# weathervane_public.net
KiCad netlist of a schematic drawn in EAGLE
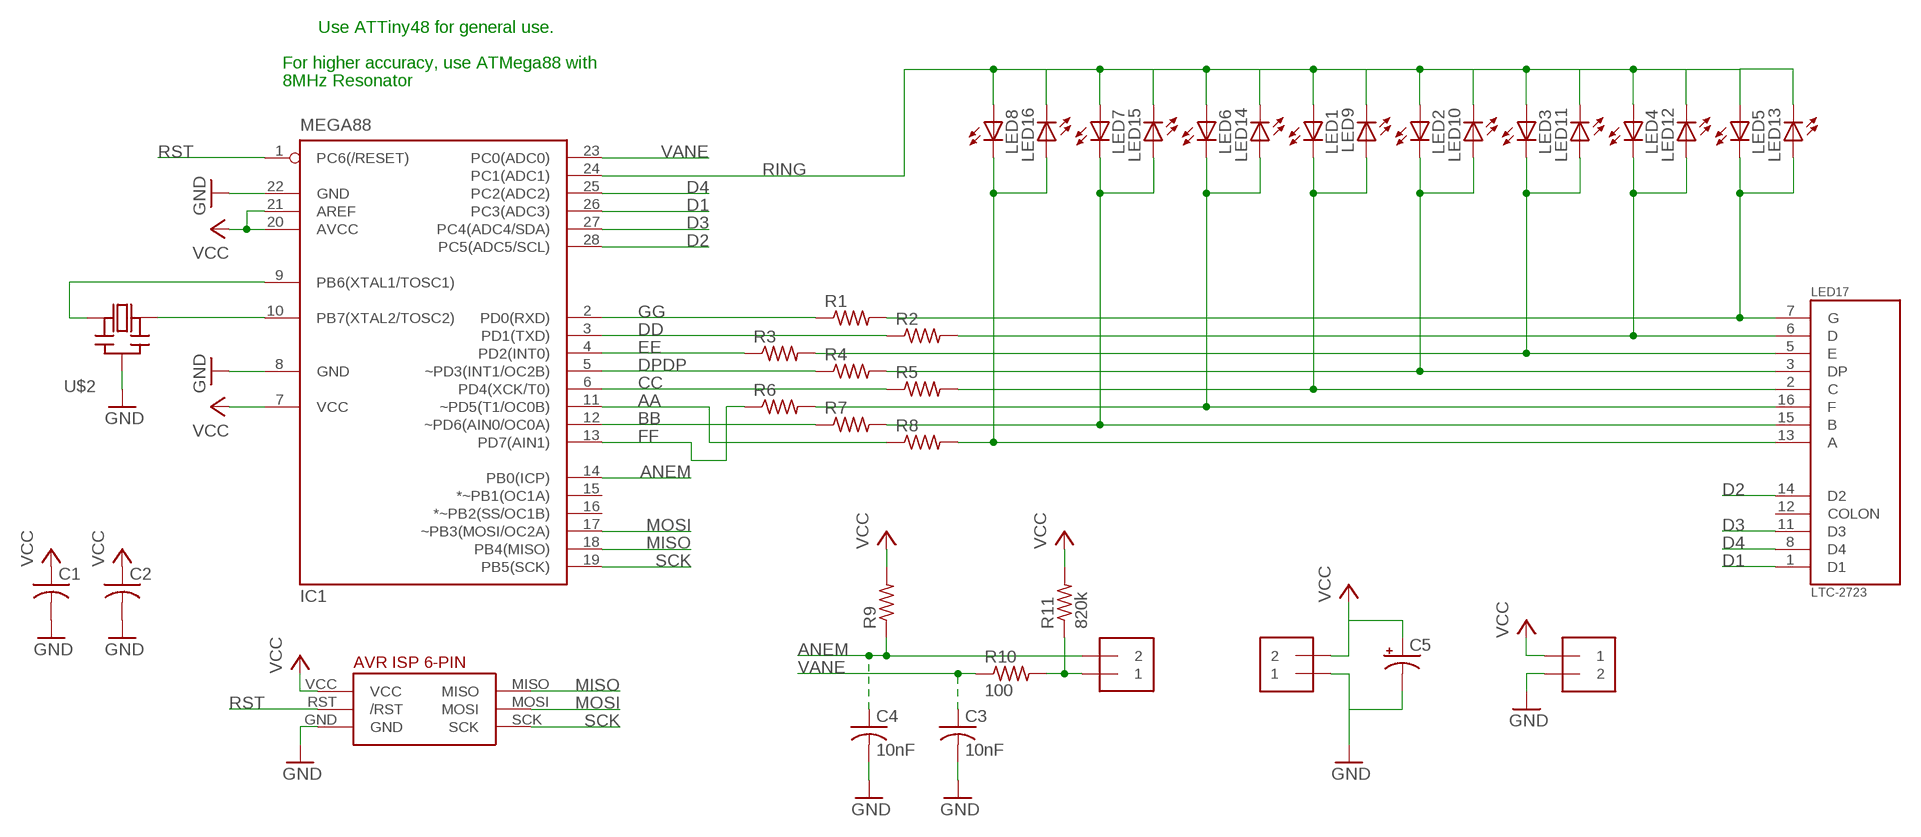
[diagram p0: schematic, sheet 1]

(export (version "E")
  (design (tool "Eeschema 10.0.6"))
  (components
    (comp (ref "C1")
      (value "C025_050X025")
      (footprint "eagle-import:C025_050X025")
      (libsource (lib "eagle-import") (part "C025_050X025"))
    )
    (comp (ref "C2")
      (value "C025_050X025")
      (footprint "eagle-import:C025_050X025")
      (libsource (lib "eagle-import") (part "C025_050X025"))
    )
    (comp (ref "C3")
      (value "10nF")
      (footprint "eagle-import:C025_050X025")
      (libsource (lib "eagle-import") (part "C025_050X025"))
    )
    (comp (ref "C4")
      (value "10nF")
      (footprint "eagle-import:C025_050X025")
      (libsource (lib "eagle-import") (part "C025_050X025"))
    )
    (comp (ref "C5")
      (value "C_POL2.5-6")
      (footprint "eagle-import:E25-6")
      (libsource (lib "eagle-import") (part "C_POL2.5-6"))
    )
    (comp (ref "IC1")
      (value "MEGA88")
      (footprint "eagle-import:DIL28-3")
      (libsource (lib "eagle-import") (part "MEGA8-P"))
    )
    (comp (ref "J1")
      (value "1X2-3.5MM")
      (footprint "eagle-import:1X2-3.5MM")
      (libsource (lib "eagle-import") (part "1X2-3.5MM"))
    )
    (comp (ref "J2")
      (value "1X2-3.5MM")
      (footprint "eagle-import:1X2-3.5MM")
      (libsource (lib "eagle-import") (part "1X2-3.5MM"))
    )
    (comp (ref "J3")
      (value "1X2-3.5MM")
      (footprint "eagle-import:1X2-3.5MM")
      (libsource (lib "eagle-import") (part "1X2-3.5MM"))
    )
    (comp (ref "LED1")
      (value "LED5MM")
      (footprint "eagle-import:LED5MM")
      (libsource (lib "eagle-import") (part "LED5MM"))
    )
    (comp (ref "LED2")
      (value "LED5MM")
      (footprint "eagle-import:LED5MM")
      (libsource (lib "eagle-import") (part "LED5MM"))
    )
    (comp (ref "LED3")
      (value "LED5MM")
      (footprint "eagle-import:LED5MM")
      (libsource (lib "eagle-import") (part "LED5MM"))
    )
    (comp (ref "LED4")
      (value "LED5MM")
      (footprint "eagle-import:LED5MM")
      (libsource (lib "eagle-import") (part "LED5MM"))
    )
    (comp (ref "LED5")
      (value "LED5MM")
      (footprint "eagle-import:LED5MM")
      (libsource (lib "eagle-import") (part "LED5MM"))
    )
    (comp (ref "LED6")
      (value "LED5MM")
      (footprint "eagle-import:LED5MM")
      (libsource (lib "eagle-import") (part "LED5MM"))
    )
    (comp (ref "LED7")
      (value "LED5MM")
      (footprint "eagle-import:LED5MM")
      (libsource (lib "eagle-import") (part "LED5MM"))
    )
    (comp (ref "LED8")
      (value "LED5MM")
      (footprint "eagle-import:LED5MM")
      (libsource (lib "eagle-import") (part "LED5MM"))
    )
    (comp (ref "LED9")
      (value "LED5MM")
      (footprint "eagle-import:LED5MM")
      (libsource (lib "eagle-import") (part "LED5MM"))
    )
    (comp (ref "LED10")
      (value "LED5MM")
      (footprint "eagle-import:LED5MM")
      (libsource (lib "eagle-import") (part "LED5MM"))
    )
    (comp (ref "LED11")
      (value "LED5MM")
      (footprint "eagle-import:LED5MM")
      (libsource (lib "eagle-import") (part "LED5MM"))
    )
    (comp (ref "LED12")
      (value "LED5MM")
      (footprint "eagle-import:LED5MM")
      (libsource (lib "eagle-import") (part "LED5MM"))
    )
    (comp (ref "LED13")
      (value "LED5MM")
      (footprint "eagle-import:LED5MM")
      (libsource (lib "eagle-import") (part "LED5MM"))
    )
    (comp (ref "LED14")
      (value "LED5MM")
      (footprint "eagle-import:LED5MM")
      (libsource (lib "eagle-import") (part "LED5MM"))
    )
    (comp (ref "LED15")
      (value "LED5MM")
      (footprint "eagle-import:LED5MM")
      (libsource (lib "eagle-import") (part "LED5MM"))
    )
    (comp (ref "LED16")
      (value "LED5MM")
      (footprint "eagle-import:LED5MM")
      (libsource (lib "eagle-import") (part "LED5MM"))
    )
    (comp (ref "LED17")
      (value "LTC-2723")
      (footprint "eagle-import:LTC-2723")
      (libsource (lib "eagle-import") (part "LTC-2723"))
    )
    (comp (ref "R1")
      (value "R207/7")
      (footprint "eagle-import:R_207_7")
      (libsource (lib "eagle-import") (part "R207/7"))
    )
    (comp (ref "R2")
      (value "R207/7")
      (footprint "eagle-import:R_207_7")
      (libsource (lib "eagle-import") (part "R207/7"))
    )
    (comp (ref "R3")
      (value "R207/7")
      (footprint "eagle-import:R_207_7")
      (libsource (lib "eagle-import") (part "R207/7"))
    )
    (comp (ref "R4")
      (value "R207/7")
      (footprint "eagle-import:R_207_7")
      (libsource (lib "eagle-import") (part "R207/7"))
    )
    (comp (ref "R5")
      (value "R207/7")
      (footprint "eagle-import:R_207_7")
      (libsource (lib "eagle-import") (part "R207/7"))
    )
    (comp (ref "R6")
      (value "R207/7")
      (footprint "eagle-import:R_207_7")
      (libsource (lib "eagle-import") (part "R207/7"))
    )
    (comp (ref "R7")
      (value "R207/7")
      (footprint "eagle-import:R_207_7")
      (libsource (lib "eagle-import") (part "R207/7"))
    )
    (comp (ref "R8")
      (value "R207/7")
      (footprint "eagle-import:R_207_7")
      (libsource (lib "eagle-import") (part "R207/7"))
    )
    (comp (ref "R9")
      (value "R207/7")
      (footprint "eagle-import:R_207_7")
      (libsource (lib "eagle-import") (part "R207/7"))
    )
    (comp (ref "R10")
      (value "100")
      (footprint "eagle-import:R_207_7")
      (libsource (lib "eagle-import") (part "R207/7"))
    )
    (comp (ref "R11")
      (value "820k")
      (footprint "eagle-import:R_207_7")
      (libsource (lib "eagle-import") (part "R207/7"))
    )
    (comp (ref "U$1")
      (value "AVR_ISP")
      (footprint "eagle-import:AVR_ISP6")
      (libsource (lib "eagle-import") (part "AVR_ISP"))
    )
    (comp (ref "U$2")
      (value "CERMOSCILL-THM")
      (footprint "eagle-import:CERM_OSC")
      (libsource (lib "eagle-import") (part "CERMOSCILL-THM"))
    )
  )
  (nets
    (net (code "1") (name "/AA") (class "Default")
      (node (ref "IC1") (pin "11") (pinfunction "~{PD5(T1/OC0B})_11") (pintype "bidirectional"))
      (node (ref "R8") (pin "1") (pinfunction "1_1") (pintype "passive"))
    )
    (net (code "2") (name "/ANEM") (class "Default")
      (node (ref "C4") (pin "1") (pinfunction "1_1") (pintype "passive"))
      (node (ref "IC1") (pin "14") (pinfunction "PB0(ICP)_14") (pintype "bidirectional"))
      (node (ref "J1") (pin "2") (pinfunction "2_2") (pintype "passive"))
      (node (ref "R9") (pin "1") (pinfunction "1_1") (pintype "passive"))
    )
    (net (code "3") (name "/BB") (class "Default")
      (node (ref "IC1") (pin "12") (pinfunction "~{PD6(AIN0/OC0A})_12") (pintype "bidirectional"))
      (node (ref "R7") (pin "1") (pinfunction "1_1") (pintype "passive"))
    )
    (net (code "4") (name "/CC") (class "Default")
      (node (ref "IC1") (pin "6") (pinfunction "PD4(XCK/T0)_6") (pintype "bidirectional"))
      (node (ref "R5") (pin "1") (pinfunction "1_1") (pintype "passive"))
    )
    (net (code "5") (name "/D1") (class "Default")
      (node (ref "IC1") (pin "26") (pinfunction "PC3(ADC3)_26") (pintype "bidirectional"))
      (node (ref "LED17") (pin "1") (pinfunction "D1_1") (pintype "bidirectional"))
    )
    (net (code "6") (name "/D2") (class "Default")
      (node (ref "IC1") (pin "28") (pinfunction "PC5(ADC5/SCL)_28") (pintype "bidirectional"))
      (node (ref "LED17") (pin "14") (pinfunction "D2_14") (pintype "bidirectional"))
    )
    (net (code "7") (name "/D3") (class "Default")
      (node (ref "IC1") (pin "27") (pinfunction "PC4(ADC4/SDA)_27") (pintype "bidirectional"))
      (node (ref "LED17") (pin "11") (pinfunction "D3_11") (pintype "bidirectional"))
    )
    (net (code "8") (name "/D4") (class "Default")
      (node (ref "IC1") (pin "25") (pinfunction "PC2(ADC2)_25") (pintype "bidirectional"))
      (node (ref "LED17") (pin "8") (pinfunction "D4_8") (pintype "bidirectional"))
    )
    (net (code "9") (name "/DD") (class "Default")
      (node (ref "IC1") (pin "3") (pinfunction "PD1(TXD)_3") (pintype "bidirectional"))
      (node (ref "R2") (pin "1") (pinfunction "1_1") (pintype "passive"))
    )
    (net (code "10") (name "/DPDP") (class "Default")
      (node (ref "IC1") (pin "5") (pinfunction "~{PD3(INT1/OC2B})_5") (pintype "bidirectional"))
      (node (ref "R4") (pin "1") (pinfunction "1_1") (pintype "passive"))
    )
    (net (code "11") (name "/EE") (class "Default")
      (node (ref "IC1") (pin "4") (pinfunction "PD2(INT0)_4") (pintype "bidirectional"))
      (node (ref "R3") (pin "1") (pinfunction "1_1") (pintype "passive"))
    )
    (net (code "12") (name "/FF") (class "Default")
      (node (ref "IC1") (pin "13") (pinfunction "PD7(AIN1)_13") (pintype "bidirectional"))
      (node (ref "R6") (pin "1") (pinfunction "1_1") (pintype "passive"))
    )
    (net (code "13") (name "/GG") (class "Default")
      (node (ref "IC1") (pin "2") (pinfunction "PD0(RXD)_2") (pintype "bidirectional"))
      (node (ref "R1") (pin "1") (pinfunction "1_1") (pintype "passive"))
    )
    (net (code "14") (name "/MISO") (class "Default")
      (node (ref "IC1") (pin "18") (pinfunction "PB4(MISO)_18") (pintype "bidirectional"))
      (node (ref "U$1") (pin "MISO") (pinfunction "MISO_MISO") (pintype "bidirectional"))
    )
    (net (code "15") (name "/MOSI") (class "Default")
      (node (ref "IC1") (pin "17") (pinfunction "~{PB3(MOSI/OC2A})_17") (pintype "bidirectional"))
      (node (ref "U$1") (pin "MOSI") (pinfunction "MOSI_MOSI") (pintype "bidirectional"))
    )
    (net (code "16") (name "/RING") (class "Default")
      (node (ref "IC1") (pin "24") (pinfunction "PC1(ADC1)_24") (pintype "bidirectional"))
      (node (ref "LED1") (pin "A") (pinfunction "A_A") (pintype "passive"))
      (node (ref "LED10") (pin "K") (pinfunction "C_K") (pintype "passive"))
      (node (ref "LED11") (pin "K") (pinfunction "C_K") (pintype "passive"))
      (node (ref "LED12") (pin "K") (pinfunction "C_K") (pintype "passive"))
      (node (ref "LED13") (pin "K") (pinfunction "C_K") (pintype "passive"))
      (node (ref "LED14") (pin "K") (pinfunction "C_K") (pintype "passive"))
      (node (ref "LED15") (pin "K") (pinfunction "C_K") (pintype "passive"))
      (node (ref "LED16") (pin "K") (pinfunction "C_K") (pintype "passive"))
      (node (ref "LED2") (pin "A") (pinfunction "A_A") (pintype "passive"))
      (node (ref "LED3") (pin "A") (pinfunction "A_A") (pintype "passive"))
      (node (ref "LED4") (pin "A") (pinfunction "A_A") (pintype "passive"))
      (node (ref "LED5") (pin "A") (pinfunction "A_A") (pintype "passive"))
      (node (ref "LED6") (pin "A") (pinfunction "A_A") (pintype "passive"))
      (node (ref "LED7") (pin "A") (pinfunction "A_A") (pintype "passive"))
      (node (ref "LED8") (pin "A") (pinfunction "A_A") (pintype "passive"))
      (node (ref "LED9") (pin "K") (pinfunction "C_K") (pintype "passive"))
    )
    (net (code "17") (name "/RST") (class "Default")
      (node (ref "IC1") (pin "1") (pinfunction "PC6(/RESET)_1") (pintype "bidirectional"))
      (node (ref "U$1") (pin "RST") (pinfunction "/RST_RST") (pintype "bidirectional"))
    )
    (net (code "18") (name "/SCK") (class "Default")
      (node (ref "IC1") (pin "19") (pinfunction "PB5(SCK)_19") (pintype "bidirectional"))
      (node (ref "U$1") (pin "SCK") (pinfunction "SCK_SCK") (pintype "bidirectional"))
    )
    (net (code "19") (name "/VANE") (class "Default")
      (node (ref "C3") (pin "1") (pinfunction "1_1") (pintype "passive"))
      (node (ref "IC1") (pin "23") (pinfunction "PC0(ADC0)_23") (pintype "bidirectional"))
      (node (ref "R10") (pin "1") (pinfunction "1_1") (pintype "passive"))
    )
    (net (code "20") (name "GND") (class "Default")
      (node (ref "C1") (pin "2") (pinfunction "2_2") (pintype "passive"))
      (node (ref "C2") (pin "2") (pinfunction "2_2") (pintype "passive"))
      (node (ref "C3") (pin "2") (pinfunction "2_2") (pintype "passive"))
      (node (ref "C4") (pin "2") (pinfunction "2_2") (pintype "passive"))
      (node (ref "C5") (pin "-") (pinfunction "-_-") (pintype "passive"))
      (node (ref "IC1") (pin "22") (pinfunction "GND_22") (pintype "power_in"))
      (node (ref "IC1") (pin "8") (pinfunction "GND_8") (pintype "power_in"))
      (node (ref "J2") (pin "2") (pinfunction "2_2") (pintype "passive"))
      (node (ref "J3") (pin "1") (pinfunction "1_1") (pintype "passive"))
      (node (ref "U$1") (pin "GND") (pinfunction "GND_GND") (pintype "power_in"))
      (node (ref "U$2") (pin "P$2") (pinfunction "GND_P$2") (pintype "bidirectional"))
    )
    (net (code "21") (name "Net-(IC1-PB6(XTAL1{slash}TOSC1))") (class "Default")
      (node (ref "IC1") (pin "9") (pinfunction "PB6(XTAL1/TOSC1)_9") (pintype "bidirectional"))
      (node (ref "U$2") (pin "P$1") (pinfunction "IN_P$1") (pintype "bidirectional"))
    )
    (net (code "22") (name "Net-(IC1-PB7(XTAL2{slash}TOSC2))") (class "Default")
      (node (ref "IC1") (pin "10") (pinfunction "PB7(XTAL2/TOSC2)_10") (pintype "bidirectional"))
      (node (ref "U$2") (pin "P$3") (pinfunction "OUT_P$3") (pintype "bidirectional"))
    )
    (net (code "23") (name "Net-(J1-Pad1)") (class "Default")
      (node (ref "J1") (pin "1") (pinfunction "1_1") (pintype "passive"))
      (node (ref "R10") (pin "2") (pinfunction "2_2") (pintype "passive"))
      (node (ref "R11") (pin "1") (pinfunction "1_1") (pintype "passive"))
    )
    (net (code "24") (name "Net-(LED1-C)") (class "Default")
      (node (ref "LED1") (pin "K") (pinfunction "C_K") (pintype "passive"))
      (node (ref "LED17") (pin "2") (pinfunction "C_2") (pintype "bidirectional"))
      (node (ref "LED9") (pin "A") (pinfunction "A_A") (pintype "passive"))
      (node (ref "R5") (pin "2") (pinfunction "2_2") (pintype "passive"))
    )
    (net (code "25") (name "Net-(LED17-A)") (class "Default")
      (node (ref "LED16") (pin "A") (pinfunction "A_A") (pintype "passive"))
      (node (ref "LED17") (pin "13") (pinfunction "A_13") (pintype "bidirectional"))
      (node (ref "LED8") (pin "K") (pinfunction "C_K") (pintype "passive"))
      (node (ref "R8") (pin "2") (pinfunction "2_2") (pintype "passive"))
    )
    (net (code "26") (name "Net-(LED17-B)") (class "Default")
      (node (ref "LED15") (pin "A") (pinfunction "A_A") (pintype "passive"))
      (node (ref "LED17") (pin "15") (pinfunction "B_15") (pintype "bidirectional"))
      (node (ref "LED7") (pin "K") (pinfunction "C_K") (pintype "passive"))
      (node (ref "R7") (pin "2") (pinfunction "2_2") (pintype "passive"))
    )
    (net (code "27") (name "Net-(LED17-D)") (class "Default")
      (node (ref "LED12") (pin "A") (pinfunction "A_A") (pintype "passive"))
      (node (ref "LED17") (pin "6") (pinfunction "D_6") (pintype "bidirectional"))
      (node (ref "LED4") (pin "K") (pinfunction "C_K") (pintype "passive"))
      (node (ref "R2") (pin "2") (pinfunction "2_2") (pintype "passive"))
    )
    (net (code "28") (name "Net-(LED17-DP)") (class "Default")
      (node (ref "LED10") (pin "A") (pinfunction "A_A") (pintype "passive"))
      (node (ref "LED17") (pin "3") (pinfunction "DP_3") (pintype "bidirectional"))
      (node (ref "LED2") (pin "K") (pinfunction "C_K") (pintype "passive"))
      (node (ref "R4") (pin "2") (pinfunction "2_2") (pintype "passive"))
    )
    (net (code "29") (name "Net-(LED17-E)") (class "Default")
      (node (ref "LED11") (pin "A") (pinfunction "A_A") (pintype "passive"))
      (node (ref "LED17") (pin "5") (pinfunction "E_5") (pintype "bidirectional"))
      (node (ref "LED3") (pin "K") (pinfunction "C_K") (pintype "passive"))
      (node (ref "R3") (pin "2") (pinfunction "2_2") (pintype "passive"))
    )
    (net (code "30") (name "Net-(LED17-F)") (class "Default")
      (node (ref "LED14") (pin "A") (pinfunction "A_A") (pintype "passive"))
      (node (ref "LED17") (pin "16") (pinfunction "F_16") (pintype "bidirectional"))
      (node (ref "LED6") (pin "K") (pinfunction "C_K") (pintype "passive"))
      (node (ref "R6") (pin "2") (pinfunction "2_2") (pintype "passive"))
    )
    (net (code "31") (name "Net-(LED17-G)") (class "Default")
      (node (ref "LED13") (pin "A") (pinfunction "A_A") (pintype "passive"))
      (node (ref "LED17") (pin "7") (pinfunction "G_7") (pintype "bidirectional"))
      (node (ref "LED5") (pin "K") (pinfunction "C_K") (pintype "passive"))
      (node (ref "R1") (pin "2") (pinfunction "2_2") (pintype "passive"))
    )
    (net (code "32") (name "VCC") (class "Default")
      (node (ref "C1") (pin "1") (pinfunction "1_1") (pintype "passive"))
      (node (ref "C2") (pin "1") (pinfunction "1_1") (pintype "passive"))
      (node (ref "C5") (pin "+") (pinfunction "+_+") (pintype "passive"))
      (node (ref "IC1") (pin "20") (pinfunction "AVCC_20") (pintype "power_in"))
      (node (ref "IC1") (pin "21") (pinfunction "AREF_21") (pintype "passive"))
      (node (ref "IC1") (pin "7") (pinfunction "VCC_7") (pintype "power_in"))
      (node (ref "J2") (pin "1") (pinfunction "1_1") (pintype "passive"))
      (node (ref "J3") (pin "2") (pinfunction "2_2") (pintype "passive"))
      (node (ref "R11") (pin "2") (pinfunction "2_2") (pintype "passive"))
      (node (ref "R9") (pin "2") (pinfunction "2_2") (pintype "passive"))
      (node (ref "U$1") (pin "VCC") (pinfunction "VCC_VCC") (pintype "power_in"))
    )
    (net (code "33") (name "unconnected-(IC1-*~{PB1(OC1A})-Pad15)") (class "Default")
      (node (ref "IC1") (pin "15") (pinfunction "*~{PB1(OC1A})_15") (pintype "bidirectional"))
    )
    (net (code "34") (name "unconnected-(IC1-*~{PB2(SS{slash}OC1B})-Pad16)") (class "Default")
      (node (ref "IC1") (pin "16") (pinfunction "*~{PB2(SS/OC1B})_16") (pintype "bidirectional"))
    )
    (net (code "35") (name "unconnected-(LED17-COLON-Pad12)") (class "Default")
      (node (ref "LED17") (pin "12") (pinfunction "COLON_12") (pintype "bidirectional"))
    )
  )
)
